# CAN_Interface.net
KiCad netlist of a schematic drawn in Altium Designer
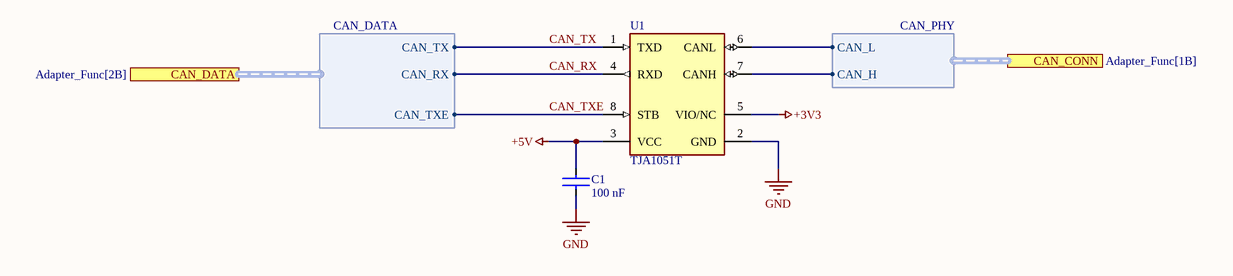
[diagram p0: CAN Interface.SchDoc]

(export (version "E")
  (design (tool "Eeschema 10.0.6"))
  (components
    (comp (ref "C1")
      (value "100 nF")
      (footprint "0603 SMD CAP")
      (description "25V 100nF X7R ±10% 0603 Multilayer Ceramic Capacitors MLCC")
      (fields (field (name "PART NUMBER") "CL10B104KA8NNNC"))
      (libsource (lib "Max_lib") (part "Cap 100nF 0603"))
    )
    (comp (ref "U1")
      (value "TJA1051T")
      (footprint "SOIC-8")
      (description "TJA1051T CAN Transeiver up to 5 Mbaud/s")
      (fields (field (name "PART NUMBER") "TJA1051T,118"))
      (libsource (lib "Max_lib") (part "CAN Transeiver TJA1051T"))
    )
  )
  (nets
    (net (code "3") (name "+3V3") (class "Default")
      (node (ref "U1") (pin "5") (pinfunction "VIO/NC_5") (pintype "passive"))
    )
    (net (code "4") (name "+5V") (class "Default")
      (node (ref "C1") (pin "2") (pinfunction "2_2") (pintype "passive"))
      (node (ref "U1") (pin "3") (pinfunction "VCC_3") (pintype "power_in"))
    )
    (net (code "5") (name "/CAN_H") (class "Default")
      (node (ref "U1") (pin "7") (pinfunction "CANH_7") (pintype "bidirectional"))
    )
    (net (code "6") (name "/CAN_L") (class "Default")
      (node (ref "U1") (pin "6") (pinfunction "CANL_6") (pintype "bidirectional"))
    )
    (net (code "7") (name "/CAN_RX") (class "Default")
      (node (ref "U1") (pin "4") (pinfunction "RXD_4") (pintype "output"))
    )
    (net (code "8") (name "/CAN_TX") (class "Default")
      (node (ref "U1") (pin "1") (pinfunction "TXD_1") (pintype "input"))
    )
    (net (code "9") (name "/CAN_TXE") (class "Default")
      (node (ref "U1") (pin "8") (pinfunction "STB_8") (pintype "input"))
    )
    (net (code "12") (name "GND") (class "Default")
      (node (ref "C1") (pin "1") (pinfunction "1_1") (pintype "passive"))
      (node (ref "U1") (pin "2") (pinfunction "GND_2") (pintype "power_in"))
    )
  )
)
